# single_channel.net
KiCad netlist of a schematic drawn in EAGLE
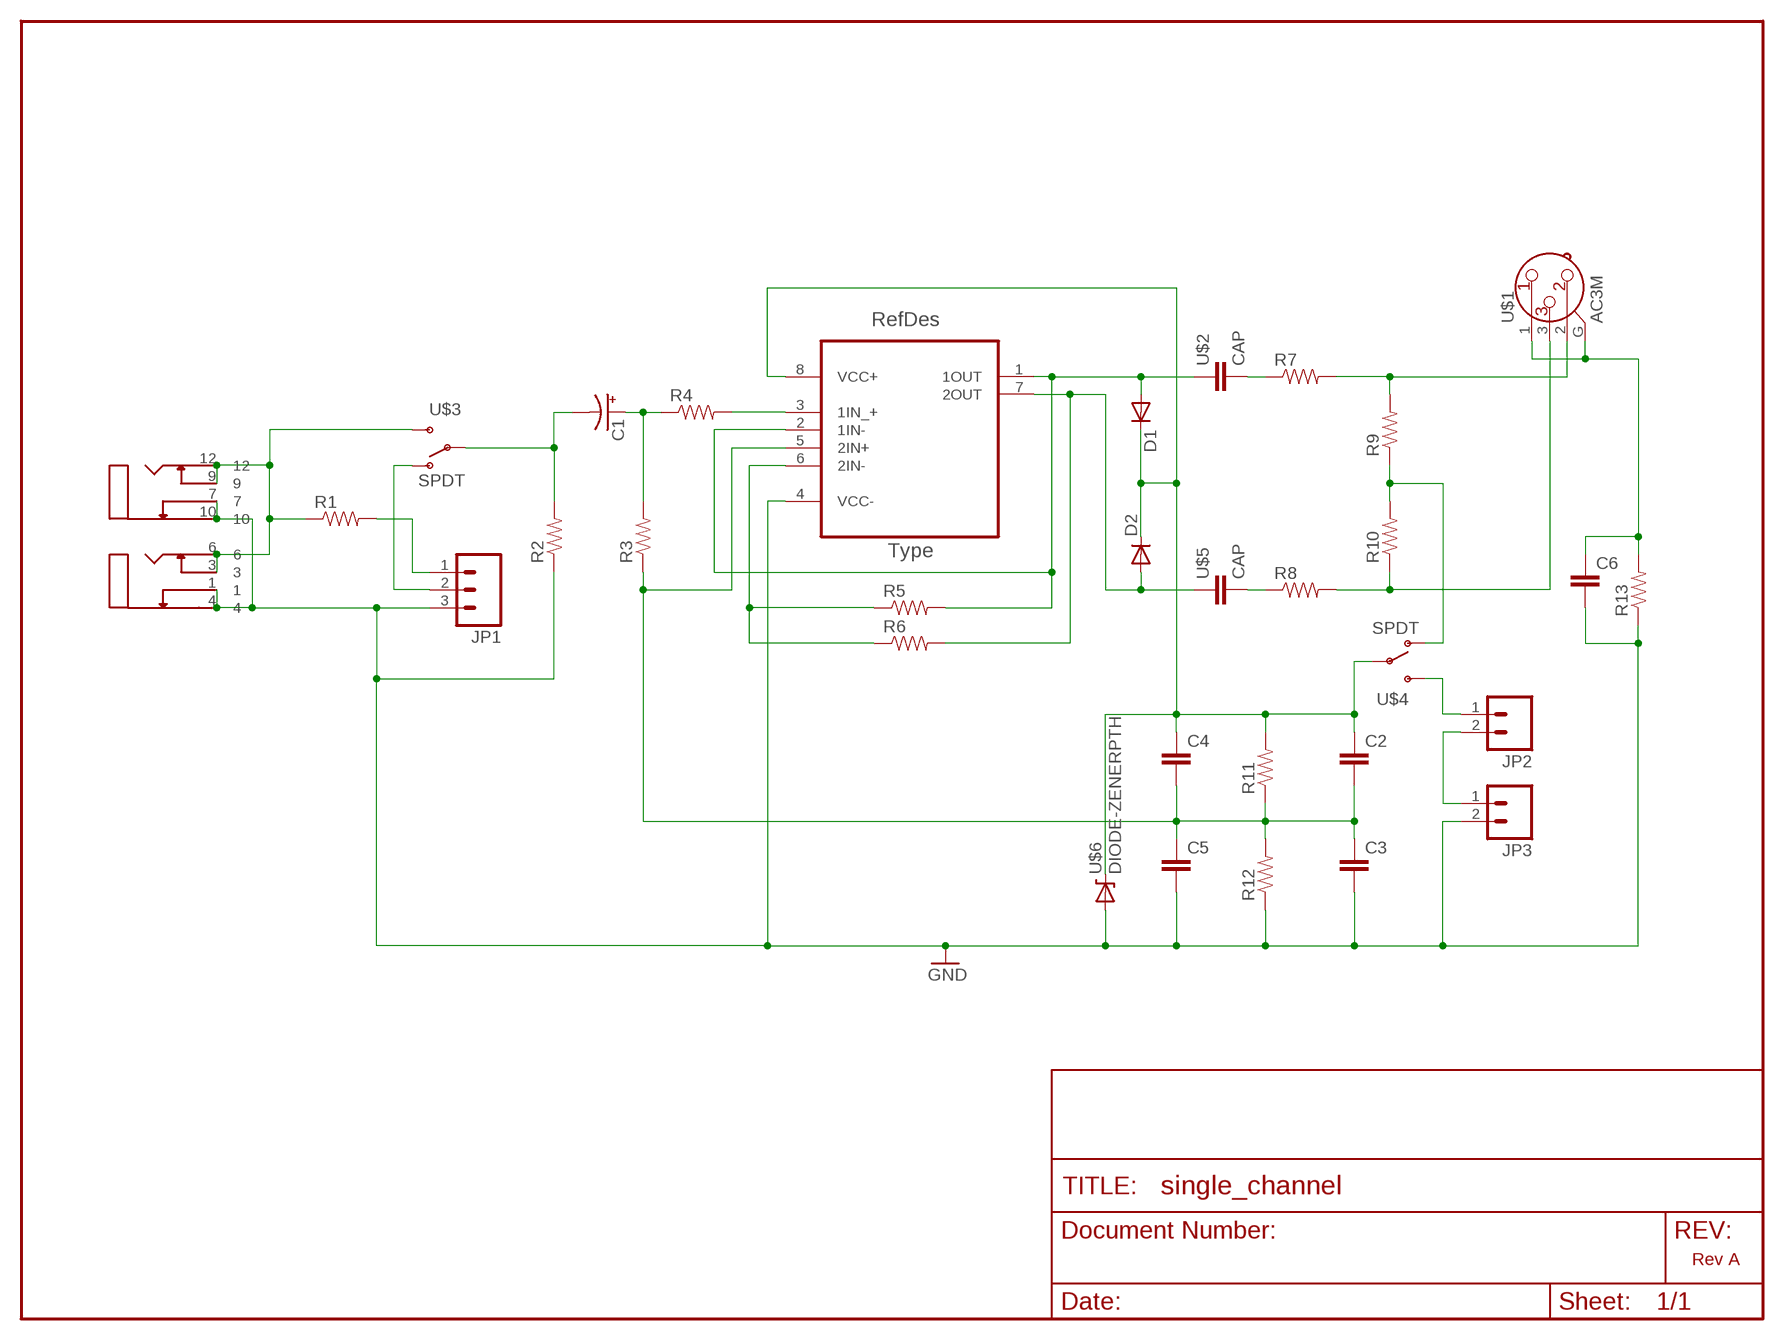
[diagram p0: schematic, sheet 1]

(export (version "E")
  (design (tool "Eeschema 10.0.6"))
  (components
    (comp (ref "C1")
      (value "CAP_POLPTH2")
      (footprint "eagle-import:CPOL-RADIAL-10UF-25V")
      (libsource (lib "eagle-import") (part "CAP_POLPTH2"))
    )
    (comp (ref "C2")
      (value "C27/11")
      (footprint "eagle-import:C27.5B11")
      (libsource (lib "eagle-import") (part "C27/11"))
    )
    (comp (ref "C3")
      (value "C27/11")
      (footprint "eagle-import:C27.5B11")
      (libsource (lib "eagle-import") (part "C27/11"))
    )
    (comp (ref "C4")
      (value "CAPPTH1")
      (footprint "eagle-import:CAP-PTH-5MM")
      (libsource (lib "eagle-import") (part "CAPPTH1"))
    )
    (comp (ref "C5")
      (value "CAPPTH1")
      (footprint "eagle-import:CAP-PTH-5MM")
      (libsource (lib "eagle-import") (part "CAPPTH1"))
    )
    (comp (ref "C6")
      (value "CAPPTH1")
      (footprint "eagle-import:CAP-PTH-5MM")
      (libsource (lib "eagle-import") (part "CAPPTH1"))
    )
    (comp (ref "D1")
      (value "DIODE1N4148")
      (footprint "eagle-import:DIODE-1N4148")
      (libsource (lib "eagle-import") (part "DIODE1N4148"))
    )
    (comp (ref "D2")
      (value "DIODE1N4148")
      (footprint "eagle-import:DIODE-1N4148")
      (libsource (lib "eagle-import") (part "DIODE1N4148"))
    )
    (comp (ref "J1")
      (value "ACJMMHD")
      (footprint "eagle-import:MHD")
      (libsource (lib "eagle-import") (part "ACJMMHD"))
    )
    (comp (ref "JP1")
      (value "M03LONGPADS")
      (footprint "eagle-import:1X03_LONGPADS")
      (libsource (lib "eagle-import") (part "M03LONGPADS"))
    )
    (comp (ref "JP2")
      (value "M02PTH3")
      (footprint "eagle-import:1X02_LONGPADS")
      (libsource (lib "eagle-import") (part "M02PTH3"))
    )
    (comp (ref "JP3")
      (value "M02PTH3")
      (footprint "eagle-import:1X02_LONGPADS")
      (libsource (lib "eagle-import") (part "M02PTH3"))
    )
    (comp (ref "R1")
      (value "RESISTORPTH-1/2W")
      (footprint "eagle-import:AXIAL-0.5")
      (libsource (lib "eagle-import") (part "RESISTORPTH-1/2W"))
    )
    (comp (ref "R2")
      (value "RESISTORPTH-1/2W")
      (footprint "eagle-import:AXIAL-0.5")
      (libsource (lib "eagle-import") (part "RESISTORPTH-1/2W"))
    )
    (comp (ref "R3")
      (value "RESISTORPTH-1/2W")
      (footprint "eagle-import:AXIAL-0.5")
      (libsource (lib "eagle-import") (part "RESISTORPTH-1/2W"))
    )
    (comp (ref "R4")
      (value "RESISTORPTH-1/2W")
      (footprint "eagle-import:AXIAL-0.5")
      (libsource (lib "eagle-import") (part "RESISTORPTH-1/2W"))
    )
    (comp (ref "R5")
      (value "RESISTORPTH-1/2W")
      (footprint "eagle-import:AXIAL-0.5")
      (libsource (lib "eagle-import") (part "RESISTORPTH-1/2W"))
    )
    (comp (ref "R6")
      (value "RESISTORPTH-1/2W")
      (footprint "eagle-import:AXIAL-0.5")
      (libsource (lib "eagle-import") (part "RESISTORPTH-1/2W"))
    )
    (comp (ref "R7")
      (value "RESISTORPTH-1/2W")
      (footprint "eagle-import:AXIAL-0.5")
      (libsource (lib "eagle-import") (part "RESISTORPTH-1/2W"))
    )
    (comp (ref "R8")
      (value "RESISTORPTH-1/2W")
      (footprint "eagle-import:AXIAL-0.5")
      (libsource (lib "eagle-import") (part "RESISTORPTH-1/2W"))
    )
    (comp (ref "R9")
      (value "RESISTORPTH-1/2W")
      (footprint "eagle-import:AXIAL-0.5")
      (libsource (lib "eagle-import") (part "RESISTORPTH-1/2W"))
    )
    (comp (ref "R10")
      (value "RESISTORPTH-1/2W")
      (footprint "eagle-import:AXIAL-0.5")
      (libsource (lib "eagle-import") (part "RESISTORPTH-1/2W"))
    )
    (comp (ref "R11")
      (value "RESISTORPTH-1/2W")
      (footprint "eagle-import:AXIAL-0.5")
      (libsource (lib "eagle-import") (part "RESISTORPTH-1/2W"))
    )
    (comp (ref "R12")
      (value "RESISTORPTH-1/2W")
      (footprint "eagle-import:AXIAL-0.5")
      (libsource (lib "eagle-import") (part "RESISTORPTH-1/2W"))
    )
    (comp (ref "R13")
      (value "RESISTORPTH-1/2W")
      (footprint "eagle-import:AXIAL-0.5")
      (libsource (lib "eagle-import") (part "RESISTORPTH-1/2W"))
    )
    (comp (ref "U$1")
      (value "AC3M")
      (footprint "eagle-import:AC3MAH")
      (libsource (lib "eagle-import") (part "AC3M"))
    )
    (comp (ref "U$2")
      (value "CAP")
      (footprint "eagle-import:C1812")
      (libsource (lib "eagle-import") (part "CAP"))
    )
    (comp (ref "U$3")
      (value "SPDT")
      (footprint "eagle-import:SPDT-SLIDE")
      (libsource (lib "eagle-import") (part "SPDT"))
    )
    (comp (ref "U$4")
      (value "SPDT")
      (footprint "eagle-import:SPDT-SLIDE")
      (libsource (lib "eagle-import") (part "SPDT"))
    )
    (comp (ref "U$5")
      (value "CAP")
      (footprint "eagle-import:C1812")
      (libsource (lib "eagle-import") (part "CAP"))
    )
    (comp (ref "U$6")
      (value "DIODE-ZENERPTH")
      (footprint "eagle-import:DIODE-ZENER")
      (libsource (lib "eagle-import") (part "DIODE-ZENERPTH"))
    )
    (comp (ref "U1")
      (value "TL072CP")
      (footprint "eagle-import:DIP254P762X508-8")
      (libsource (lib "eagle-import") (part "TL072CP"))
    )
  )
  (nets
    (net (code "1") (name "GND") (class "Default")
      (node (ref "C3") (pin "2") (pinfunction "2_2") (pintype "passive"))
      (node (ref "C5") (pin "2") (pinfunction "2_2") (pintype "passive"))
      (node (ref "C6") (pin "2") (pinfunction "2_2") (pintype "passive"))
      (node (ref "J1") (pin "1") (pinfunction "1_1") (pintype "bidirectional"))
      (node (ref "J1") (pin "10") (pinfunction "10_10") (pintype "bidirectional"))
      (node (ref "J1") (pin "4") (pinfunction "4_4") (pintype "bidirectional"))
      (node (ref "J1") (pin "7") (pinfunction "7_7") (pintype "bidirectional"))
      (node (ref "JP1") (pin "3") (pinfunction "3_3") (pintype "passive"))
      (node (ref "JP3") (pin "2") (pinfunction "2_2") (pintype "passive"))
      (node (ref "R12") (pin "P$1") (pinfunction "1_P$1") (pintype "passive"))
      (node (ref "R13") (pin "P$1") (pinfunction "1_P$1") (pintype "passive"))
      (node (ref "R2") (pin "P$1") (pinfunction "1_P$1") (pintype "passive"))
      (node (ref "U$6") (pin "P$2") (pinfunction "A_P$2") (pintype "passive"))
      (node (ref "U1") (pin "4") (pinfunction "VCC-_4") (pintype "passive"))
    )
    (net (code "2") (name "Net-(C1-+)") (class "Default")
      (node (ref "C1") (pin "1") (pinfunction "+_1") (pintype "passive"))
      (node (ref "R3") (pin "P$2") (pinfunction "2_P$2") (pintype "passive"))
      (node (ref "R4") (pin "P$1") (pinfunction "1_P$1") (pintype "passive"))
    )
    (net (code "3") (name "Net-(C1--)") (class "Default")
      (node (ref "C1") (pin "2") (pinfunction "-_2") (pintype "passive"))
      (node (ref "R2") (pin "P$2") (pinfunction "2_P$2") (pintype "passive"))
      (node (ref "U$3") (pin "2") (pinfunction "2_2") (pintype "passive"))
    )
    (net (code "4") (name "Net-(JP1-Pad2)") (class "Default")
      (node (ref "JP1") (pin "2") (pinfunction "2_2") (pintype "passive"))
      (node (ref "U$3") (pin "1") (pinfunction "1_1") (pintype "passive"))
    )
    (net (code "5") (name "Net-(JP2-Pad1)") (class "Default")
      (node (ref "JP2") (pin "1") (pinfunction "1_1") (pintype "passive"))
      (node (ref "U$4") (pin "3") (pinfunction "3_3") (pintype "passive"))
    )
    (net (code "6") (name "Net-(JP2-Pad2)") (class "Default")
      (node (ref "JP2") (pin "2") (pinfunction "2_2") (pintype "passive"))
      (node (ref "JP3") (pin "1") (pinfunction "1_1") (pintype "passive"))
    )
    (net (code "7") (name "Net-(R1-1)") (class "Default")
      (node (ref "J1") (pin "12") (pinfunction "12_12") (pintype "bidirectional"))
      (node (ref "J1") (pin "3") (pinfunction "3_3") (pintype "bidirectional"))
      (node (ref "J1") (pin "6") (pinfunction "6_6") (pintype "bidirectional"))
      (node (ref "J1") (pin "9") (pinfunction "9_9") (pintype "bidirectional"))
      (node (ref "R1") (pin "P$1") (pinfunction "1_P$1") (pintype "passive"))
      (node (ref "U$3") (pin "3") (pinfunction "3_3") (pintype "passive"))
    )
    (net (code "8") (name "Net-(R1-2)") (class "Default")
      (node (ref "JP1") (pin "1") (pinfunction "1_1") (pintype "passive"))
      (node (ref "R1") (pin "P$2") (pinfunction "2_P$2") (pintype "passive"))
    )
    (net (code "9") (name "Net-(R4-2)") (class "Default")
      (node (ref "R4") (pin "P$2") (pinfunction "2_P$2") (pintype "passive"))
      (node (ref "U1") (pin "3") (pinfunction "1IN_+_3") (pintype "input"))
    )
    (net (code "10") (name "Net-(R5-1)") (class "Default")
      (node (ref "R5") (pin "P$1") (pinfunction "1_P$1") (pintype "passive"))
      (node (ref "R6") (pin "P$1") (pinfunction "1_P$1") (pintype "passive"))
      (node (ref "U1") (pin "6") (pinfunction "2IN-_6") (pintype "input"))
    )
    (net (code "11") (name "Net-(R5-2)") (class "Default")
      (node (ref "D1") (pin "A") (pinfunction "A_A") (pintype "passive"))
      (node (ref "R5") (pin "P$2") (pinfunction "2_P$2") (pintype "passive"))
      (node (ref "U$2") (pin "1") (pinfunction "1_1") (pintype "passive"))
      (node (ref "U1") (pin "1") (pinfunction "1OUT_1") (pintype "output"))
      (node (ref "U1") (pin "2") (pinfunction "1IN-_2") (pintype "input"))
    )
    (net (code "12") (name "Net-(R6-2)") (class "Default")
      (node (ref "D2") (pin "A") (pinfunction "A_A") (pintype "passive"))
      (node (ref "R6") (pin "P$2") (pinfunction "2_P$2") (pintype "passive"))
      (node (ref "U$5") (pin "1") (pinfunction "1_1") (pintype "passive"))
      (node (ref "U1") (pin "7") (pinfunction "2OUT_7") (pintype "output"))
    )
    (net (code "13") (name "Net-(R7-1)") (class "Default")
      (node (ref "R7") (pin "P$1") (pinfunction "1_P$1") (pintype "passive"))
      (node (ref "U$2") (pin "2") (pinfunction "2_2") (pintype "passive"))
    )
    (net (code "14") (name "Net-(R7-2)") (class "Default")
      (node (ref "R7") (pin "P$2") (pinfunction "2_P$2") (pintype "passive"))
      (node (ref "R9") (pin "P$2") (pinfunction "2_P$2") (pintype "passive"))
      (node (ref "U$1") (pin "2") (pinfunction "2_2") (pintype "passive"))
    )
    (net (code "15") (name "Net-(R8-1)") (class "Default")
      (node (ref "R8") (pin "P$1") (pinfunction "1_P$1") (pintype "passive"))
      (node (ref "U$5") (pin "2") (pinfunction "2_2") (pintype "passive"))
    )
    (net (code "16") (name "Net-(R10-1)") (class "Default")
      (node (ref "R10") (pin "P$1") (pinfunction "1_P$1") (pintype "passive"))
      (node (ref "R8") (pin "P$2") (pinfunction "2_P$2") (pintype "passive"))
      (node (ref "U$1") (pin "3") (pinfunction "3_3") (pintype "passive"))
    )
    (net (code "17") (name "Net-(R10-2)") (class "Default")
      (node (ref "R10") (pin "P$2") (pinfunction "2_P$2") (pintype "passive"))
      (node (ref "R9") (pin "P$1") (pinfunction "1_P$1") (pintype "passive"))
      (node (ref "U$4") (pin "1") (pinfunction "1_1") (pintype "passive"))
    )
    (net (code "18") (name "Net-(R11-1)") (class "Default")
      (node (ref "C2") (pin "2") (pinfunction "2_2") (pintype "passive"))
      (node (ref "C3") (pin "1") (pinfunction "1_1") (pintype "passive"))
      (node (ref "C4") (pin "2") (pinfunction "2_2") (pintype "passive"))
      (node (ref "C5") (pin "1") (pinfunction "1_1") (pintype "passive"))
      (node (ref "R11") (pin "P$1") (pinfunction "1_P$1") (pintype "passive"))
      (node (ref "R12") (pin "P$2") (pinfunction "2_P$2") (pintype "passive"))
      (node (ref "R3") (pin "P$1") (pinfunction "1_P$1") (pintype "passive"))
      (node (ref "U1") (pin "5") (pinfunction "2IN+_5") (pintype "input"))
    )
    (net (code "19") (name "Net-(R11-2)") (class "Default")
      (node (ref "C2") (pin "1") (pinfunction "1_1") (pintype "passive"))
      (node (ref "C4") (pin "1") (pinfunction "1_1") (pintype "passive"))
      (node (ref "D1") (pin "C") (pinfunction "C_C") (pintype "passive"))
      (node (ref "D2") (pin "C") (pinfunction "C_C") (pintype "passive"))
      (node (ref "R11") (pin "P$2") (pinfunction "2_P$2") (pintype "passive"))
      (node (ref "U$4") (pin "2") (pinfunction "2_2") (pintype "passive"))
      (node (ref "U$6") (pin "P$1") (pinfunction "C_P$1") (pintype "passive"))
      (node (ref "U1") (pin "8") (pinfunction "VCC+_8") (pintype "power_in"))
    )
    (net (code "20") (name "Net-(R13-2)") (class "Default")
      (node (ref "C6") (pin "1") (pinfunction "1_1") (pintype "passive"))
      (node (ref "R13") (pin "P$2") (pinfunction "2_P$2") (pintype "passive"))
      (node (ref "U$1") (pin "1") (pinfunction "1_1") (pintype "passive"))
      (node (ref "U$1") (pin "G") (pinfunction "G_G") (pintype "passive"))
    )
  )
)
